# AllPins_MCU.net
KiCad netlist of a schematic drawn in Altium Designer
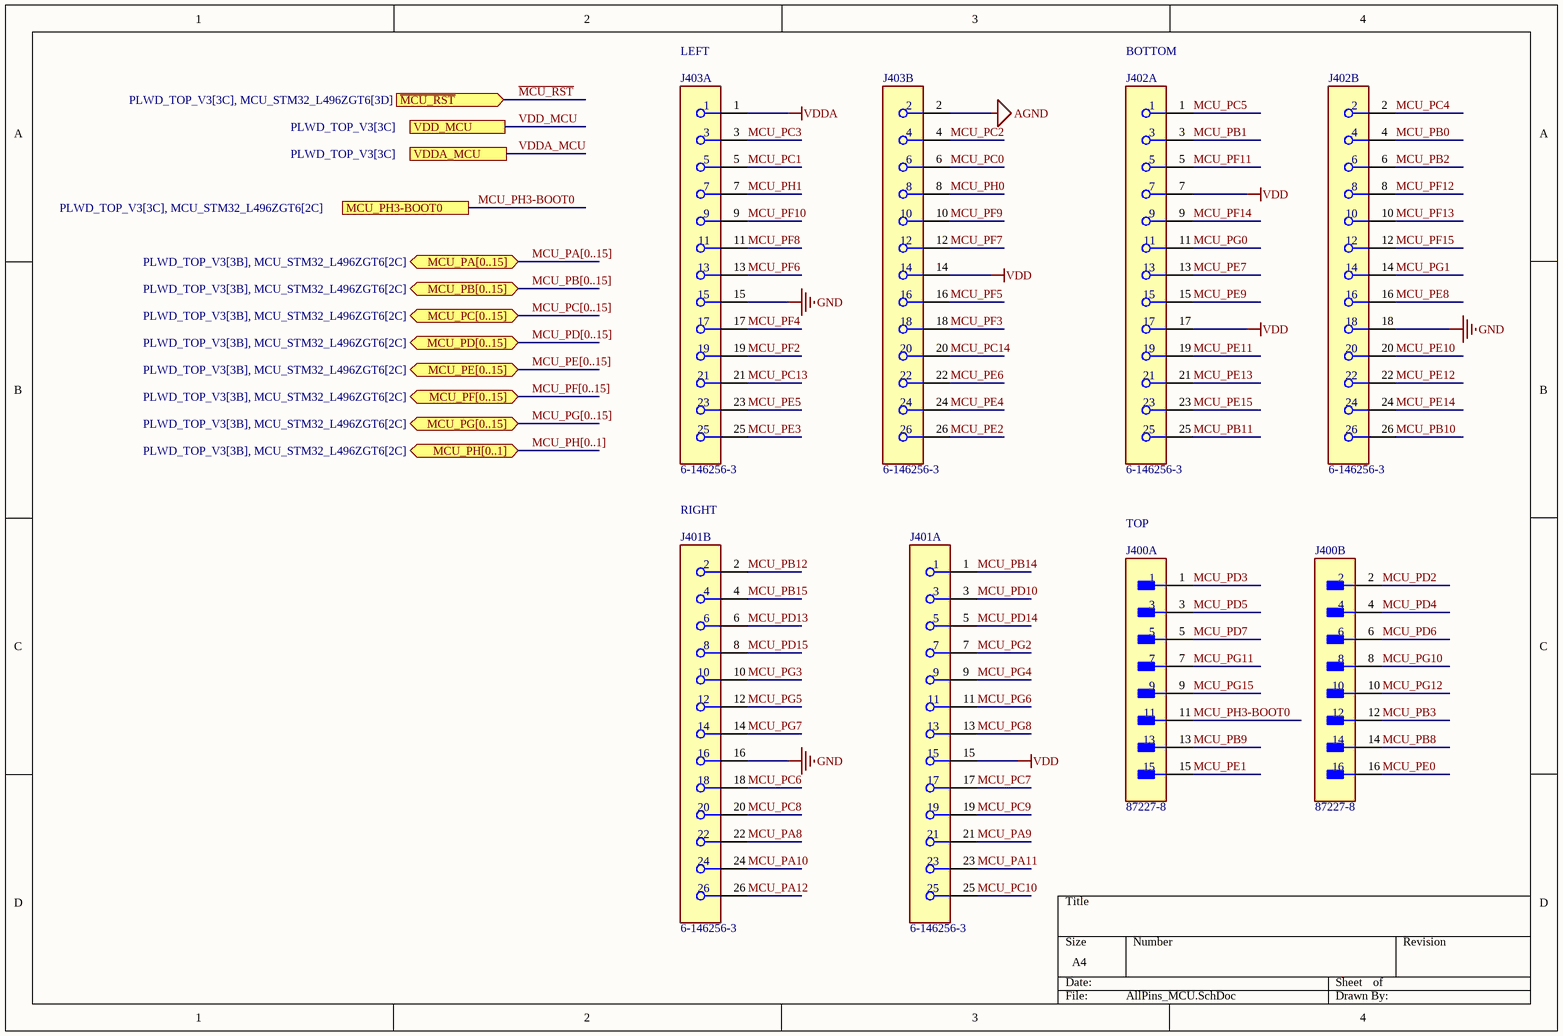
[diagram p0: AllPins_MCU.SchDoc]

(export (version "E")
  (design (tool "Eeschema 10.0.6"))
  (components
    (comp (ref "J400")
      (value "87227-8")
      (footprint "FP-87227-8-MFG")
      (description "CONN HEADER VERT 16POS 2.54MM")
      (fields
        (field (name "MANUFACTURER") "TE Connectivity")
        (field (name "OCTOPART") "https://octopart.com/87227-8-te+connectivity-39407754")
      )
      (libsource (lib "Altium Content Vault") (part "4b6d22b45e2f925f038cba5d936fbcc"))
    )
    (comp (ref "J401")
      (value "6-146256-3")
      (footprint "FP-6-146256-3-MFG")
      (description "CONN HEADER VERT 26POS 2.54MM")
      (fields
        (field (name "OCTOPART") "https://octopart.com/6-146256-3-te+connectivity-40624960")
        (field (name "MANUFACTURER") "TE Connectivity")
      )
      (libsource (lib "Altium Content Vault") (part "3742bde49fbe640198a85328faa431b"))
    )
    (comp (ref "J402")
      (value "6-146256-3")
      (footprint "FP-6-146256-3-MFG")
      (description "CONN HEADER VERT 26POS 2.54MM")
      (fields
        (field (name "OCTOPART") "https://octopart.com/6-146256-3-te+connectivity-40624960")
        (field (name "MANUFACTURER") "TE Connectivity")
      )
      (libsource (lib "Altium Content Vault") (part "3742bde49fbe640198a85328faa431b"))
    )
    (comp (ref "J403")
      (value "6-146256-3")
      (footprint "FP-6-146256-3-MFG")
      (description "CONN HEADER VERT 26POS 2.54MM")
      (fields
        (field (name "OCTOPART") "https://octopart.com/6-146256-3-te+connectivity-40624960")
        (field (name "MANUFACTURER") "TE Connectivity")
      )
      (libsource (lib "Altium Content Vault") (part "3742bde49fbe640198a85328faa431b"))
    )
  )
  (nets
    (net (code "31") (name "/MCU_PA8") (class "Default")
      (node (ref "J401") (pin "22") (pinfunction "22_22") (pintype "passive"))
    )
    (net (code "32") (name "/MCU_PA9") (class "Default")
      (node (ref "J401") (pin "21") (pinfunction "21_21") (pintype "passive"))
    )
    (net (code "33") (name "/MCU_PA10") (class "Default")
      (node (ref "J401") (pin "24") (pinfunction "24_24") (pintype "passive"))
    )
    (net (code "34") (name "/MCU_PA11") (class "Default")
      (node (ref "J401") (pin "23") (pinfunction "23_23") (pintype "passive"))
    )
    (net (code "35") (name "/MCU_PA12") (class "Default")
      (node (ref "J401") (pin "26") (pinfunction "26_26") (pintype "passive"))
    )
    (net (code "37") (name "/MCU_PB0") (class "Default")
      (node (ref "J402") (pin "4") (pinfunction "4_4") (pintype "passive"))
    )
    (net (code "38") (name "/MCU_PB1") (class "Default")
      (node (ref "J402") (pin "3") (pinfunction "3_3") (pintype "passive"))
    )
    (net (code "39") (name "/MCU_PB2") (class "Default")
      (node (ref "J402") (pin "6") (pinfunction "6_6") (pintype "passive"))
    )
    (net (code "40") (name "/MCU_PB3") (class "Default")
      (node (ref "J400") (pin "12") (pinfunction "12_12") (pintype "passive"))
    )
    (net (code "41") (name "/MCU_PB8") (class "Default")
      (node (ref "J400") (pin "14") (pinfunction "14_14") (pintype "passive"))
    )
    (net (code "42") (name "/MCU_PB9") (class "Default")
      (node (ref "J400") (pin "13") (pinfunction "13_13") (pintype "passive"))
    )
    (net (code "43") (name "/MCU_PB10") (class "Default")
      (node (ref "J402") (pin "26") (pinfunction "26_26") (pintype "passive"))
    )
    (net (code "44") (name "/MCU_PB11") (class "Default")
      (node (ref "J402") (pin "25") (pinfunction "25_25") (pintype "passive"))
    )
    (net (code "45") (name "/MCU_PB12") (class "Default")
      (node (ref "J401") (pin "2") (pinfunction "2_2") (pintype "passive"))
    )
    (net (code "46") (name "/MCU_PB14") (class "Default")
      (node (ref "J401") (pin "1") (pinfunction "1_1") (pintype "passive"))
    )
    (net (code "47") (name "/MCU_PB15") (class "Default")
      (node (ref "J401") (pin "4") (pinfunction "4_4") (pintype "passive"))
    )
    (net (code "49") (name "/MCU_PC0") (class "Default")
      (node (ref "J403") (pin "6") (pinfunction "6_6") (pintype "passive"))
    )
    (net (code "50") (name "/MCU_PC1") (class "Default")
      (node (ref "J403") (pin "5") (pinfunction "5_5") (pintype "passive"))
    )
    (net (code "51") (name "/MCU_PC2") (class "Default")
      (node (ref "J403") (pin "4") (pinfunction "4_4") (pintype "passive"))
    )
    (net (code "52") (name "/MCU_PC3") (class "Default")
      (node (ref "J403") (pin "3") (pinfunction "3_3") (pintype "passive"))
    )
    (net (code "53") (name "/MCU_PC4") (class "Default")
      (node (ref "J402") (pin "2") (pinfunction "2_2") (pintype "passive"))
    )
    (net (code "54") (name "/MCU_PC5") (class "Default")
      (node (ref "J402") (pin "1") (pinfunction "1_1") (pintype "passive"))
    )
    (net (code "55") (name "/MCU_PC6") (class "Default")
      (node (ref "J401") (pin "18") (pinfunction "18_18") (pintype "passive"))
    )
    (net (code "56") (name "/MCU_PC7") (class "Default")
      (node (ref "J401") (pin "17") (pinfunction "17_17") (pintype "passive"))
    )
    (net (code "57") (name "/MCU_PC8") (class "Default")
      (node (ref "J401") (pin "20") (pinfunction "20_20") (pintype "passive"))
    )
    (net (code "58") (name "/MCU_PC9") (class "Default")
      (node (ref "J401") (pin "19") (pinfunction "19_19") (pintype "passive"))
    )
    (net (code "59") (name "/MCU_PC10") (class "Default")
      (node (ref "J401") (pin "25") (pinfunction "25_25") (pintype "passive"))
    )
    (net (code "60") (name "/MCU_PC13") (class "Default")
      (node (ref "J403") (pin "21") (pinfunction "21_21") (pintype "passive"))
    )
    (net (code "61") (name "/MCU_PC14") (class "Default")
      (node (ref "J403") (pin "20") (pinfunction "20_20") (pintype "passive"))
    )
    (net (code "63") (name "/MCU_PD2") (class "Default")
      (node (ref "J400") (pin "2") (pinfunction "2_2") (pintype "passive"))
    )
    (net (code "64") (name "/MCU_PD3") (class "Default")
      (node (ref "J400") (pin "1") (pinfunction "1_1") (pintype "passive"))
    )
    (net (code "65") (name "/MCU_PD4") (class "Default")
      (node (ref "J400") (pin "4") (pinfunction "4_4") (pintype "passive"))
    )
    (net (code "66") (name "/MCU_PD5") (class "Default")
      (node (ref "J400") (pin "3") (pinfunction "3_3") (pintype "passive"))
    )
    (net (code "67") (name "/MCU_PD6") (class "Default")
      (node (ref "J400") (pin "6") (pinfunction "6_6") (pintype "passive"))
    )
    (net (code "68") (name "/MCU_PD7") (class "Default")
      (node (ref "J400") (pin "5") (pinfunction "5_5") (pintype "passive"))
    )
    (net (code "69") (name "/MCU_PD10") (class "Default")
      (node (ref "J401") (pin "3") (pinfunction "3_3") (pintype "passive"))
    )
    (net (code "70") (name "/MCU_PD13") (class "Default")
      (node (ref "J401") (pin "6") (pinfunction "6_6") (pintype "passive"))
    )
    (net (code "71") (name "/MCU_PD14") (class "Default")
      (node (ref "J401") (pin "5") (pinfunction "5_5") (pintype "passive"))
    )
    (net (code "72") (name "/MCU_PD15") (class "Default")
      (node (ref "J401") (pin "8") (pinfunction "8_8") (pintype "passive"))
    )
    (net (code "74") (name "/MCU_PE0") (class "Default")
      (node (ref "J400") (pin "16") (pinfunction "16_16") (pintype "passive"))
    )
    (net (code "75") (name "/MCU_PE1") (class "Default")
      (node (ref "J400") (pin "15") (pinfunction "15_15") (pintype "passive"))
    )
    (net (code "76") (name "/MCU_PE2") (class "Default")
      (node (ref "J403") (pin "26") (pinfunction "26_26") (pintype "passive"))
    )
    (net (code "77") (name "/MCU_PE3") (class "Default")
      (node (ref "J403") (pin "25") (pinfunction "25_25") (pintype "passive"))
    )
    (net (code "78") (name "/MCU_PE4") (class "Default")
      (node (ref "J403") (pin "24") (pinfunction "24_24") (pintype "passive"))
    )
    (net (code "79") (name "/MCU_PE5") (class "Default")
      (node (ref "J403") (pin "23") (pinfunction "23_23") (pintype "passive"))
    )
    (net (code "80") (name "/MCU_PE6") (class "Default")
      (node (ref "J403") (pin "22") (pinfunction "22_22") (pintype "passive"))
    )
    (net (code "81") (name "/MCU_PE7") (class "Default")
      (node (ref "J402") (pin "13") (pinfunction "13_13") (pintype "passive"))
    )
    (net (code "82") (name "/MCU_PE8") (class "Default")
      (node (ref "J402") (pin "16") (pinfunction "16_16") (pintype "passive"))
    )
    (net (code "83") (name "/MCU_PE9") (class "Default")
      (node (ref "J402") (pin "15") (pinfunction "15_15") (pintype "passive"))
    )
    (net (code "84") (name "/MCU_PE10") (class "Default")
      (node (ref "J402") (pin "20") (pinfunction "20_20") (pintype "passive"))
    )
    (net (code "85") (name "/MCU_PE11") (class "Default")
      (node (ref "J402") (pin "19") (pinfunction "19_19") (pintype "passive"))
    )
    (net (code "86") (name "/MCU_PE12") (class "Default")
      (node (ref "J402") (pin "22") (pinfunction "22_22") (pintype "passive"))
    )
    (net (code "87") (name "/MCU_PE13") (class "Default")
      (node (ref "J402") (pin "21") (pinfunction "21_21") (pintype "passive"))
    )
    (net (code "88") (name "/MCU_PE14") (class "Default")
      (node (ref "J402") (pin "24") (pinfunction "24_24") (pintype "passive"))
    )
    (net (code "89") (name "/MCU_PE15") (class "Default")
      (node (ref "J402") (pin "23") (pinfunction "23_23") (pintype "passive"))
    )
    (net (code "91") (name "/MCU_PF2") (class "Default")
      (node (ref "J403") (pin "19") (pinfunction "19_19") (pintype "passive"))
    )
    (net (code "92") (name "/MCU_PF3") (class "Default")
      (node (ref "J403") (pin "18") (pinfunction "18_18") (pintype "passive"))
    )
    (net (code "93") (name "/MCU_PF4") (class "Default")
      (node (ref "J403") (pin "17") (pinfunction "17_17") (pintype "passive"))
    )
    (net (code "94") (name "/MCU_PF5") (class "Default")
      (node (ref "J403") (pin "16") (pinfunction "16_16") (pintype "passive"))
    )
    (net (code "95") (name "/MCU_PF6") (class "Default")
      (node (ref "J403") (pin "13") (pinfunction "13_13") (pintype "passive"))
    )
    (net (code "96") (name "/MCU_PF7") (class "Default")
      (node (ref "J403") (pin "12") (pinfunction "12_12") (pintype "passive"))
    )
    (net (code "97") (name "/MCU_PF8") (class "Default")
      (node (ref "J403") (pin "11") (pinfunction "11_11") (pintype "passive"))
    )
    (net (code "98") (name "/MCU_PF9") (class "Default")
      (node (ref "J403") (pin "10") (pinfunction "10_10") (pintype "passive"))
    )
    (net (code "99") (name "/MCU_PF10") (class "Default")
      (node (ref "J403") (pin "9") (pinfunction "9_9") (pintype "passive"))
    )
    (net (code "100") (name "/MCU_PF11") (class "Default")
      (node (ref "J402") (pin "5") (pinfunction "5_5") (pintype "passive"))
    )
    (net (code "101") (name "/MCU_PF12") (class "Default")
      (node (ref "J402") (pin "8") (pinfunction "8_8") (pintype "passive"))
    )
    (net (code "102") (name "/MCU_PF13") (class "Default")
      (node (ref "J402") (pin "10") (pinfunction "10_10") (pintype "passive"))
    )
    (net (code "103") (name "/MCU_PF14") (class "Default")
      (node (ref "J402") (pin "9") (pinfunction "9_9") (pintype "passive"))
    )
    (net (code "104") (name "/MCU_PF15") (class "Default")
      (node (ref "J402") (pin "12") (pinfunction "12_12") (pintype "passive"))
    )
    (net (code "106") (name "/MCU_PG0") (class "Default")
      (node (ref "J402") (pin "11") (pinfunction "11_11") (pintype "passive"))
    )
    (net (code "107") (name "/MCU_PG1") (class "Default")
      (node (ref "J402") (pin "14") (pinfunction "14_14") (pintype "passive"))
    )
    (net (code "108") (name "/MCU_PG2") (class "Default")
      (node (ref "J401") (pin "7") (pinfunction "7_7") (pintype "passive"))
    )
    (net (code "109") (name "/MCU_PG3") (class "Default")
      (node (ref "J401") (pin "10") (pinfunction "10_10") (pintype "passive"))
    )
    (net (code "110") (name "/MCU_PG4") (class "Default")
      (node (ref "J401") (pin "9") (pinfunction "9_9") (pintype "passive"))
    )
    (net (code "111") (name "/MCU_PG5") (class "Default")
      (node (ref "J401") (pin "12") (pinfunction "12_12") (pintype "passive"))
    )
    (net (code "112") (name "/MCU_PG6") (class "Default")
      (node (ref "J401") (pin "11") (pinfunction "11_11") (pintype "passive"))
    )
    (net (code "113") (name "/MCU_PG7") (class "Default")
      (node (ref "J401") (pin "14") (pinfunction "14_14") (pintype "passive"))
    )
    (net (code "114") (name "/MCU_PG8") (class "Default")
      (node (ref "J401") (pin "13") (pinfunction "13_13") (pintype "passive"))
    )
    (net (code "115") (name "/MCU_PG10") (class "Default")
      (node (ref "J400") (pin "8") (pinfunction "8_8") (pintype "passive"))
    )
    (net (code "116") (name "/MCU_PG11") (class "Default")
      (node (ref "J400") (pin "7") (pinfunction "7_7") (pintype "passive"))
    )
    (net (code "117") (name "/MCU_PG12") (class "Default")
      (node (ref "J400") (pin "10") (pinfunction "10_10") (pintype "passive"))
    )
    (net (code "118") (name "/MCU_PG15") (class "Default")
      (node (ref "J400") (pin "9") (pinfunction "9_9") (pintype "passive"))
    )
    (net (code "120") (name "/MCU_PH0") (class "Default")
      (node (ref "J403") (pin "8") (pinfunction "8_8") (pintype "passive"))
    )
    (net (code "121") (name "/MCU_PH1") (class "Default")
      (node (ref "J403") (pin "7") (pinfunction "7_7") (pintype "passive"))
    )
    (net (code "122") (name "/MCU_PH3-BOOT0") (class "Default")
      (node (ref "J400") (pin "11") (pinfunction "11_11") (pintype "passive"))
    )
    (net (code "127") (name "AGND") (class "Default")
      (node (ref "J403") (pin "2") (pinfunction "2_2") (pintype "passive"))
    )
    (net (code "128") (name "GND") (class "Default")
      (node (ref "J401") (pin "16") (pinfunction "16_16") (pintype "passive"))
      (node (ref "J402") (pin "18") (pinfunction "18_18") (pintype "passive"))
      (node (ref "J403") (pin "15") (pinfunction "15_15") (pintype "passive"))
    )
    (net (code "129") (name "VDD") (class "Default")
      (node (ref "J401") (pin "15") (pinfunction "15_15") (pintype "passive"))
      (node (ref "J402") (pin "17") (pinfunction "17_17") (pintype "passive"))
      (node (ref "J402") (pin "7") (pinfunction "7_7") (pintype "passive"))
      (node (ref "J403") (pin "14") (pinfunction "14_14") (pintype "passive"))
    )
    (net (code "130") (name "VDDA") (class "Default")
      (node (ref "J403") (pin "1") (pinfunction "1_1") (pintype "passive"))
    )
  )
)
